# tps79333.net
KiCad netlist of a schematic drawn in Altium Designer
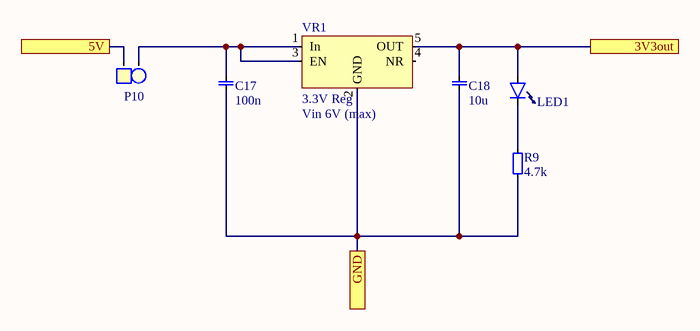
[diagram p0: tps79333.SchDoc]

(export (version "E")
  (design (tool "Eeschema 10.0.6"))
  (components
    (comp (ref "C17")
      (value "100n")
      (footprint "1206, capasitor")
      (fields (field (name "Comment") "1206, capacitor"))
      (libsource (lib "eitp15_lab1_lib") (part "1206, capacitor"))
    )
    (comp (ref "C18")
      (value "10u")
      (footprint "1206, capasitor")
      (fields (field (name "Comment") "1206, capacitor"))
      (libsource (lib "eitp15_lab1_lib") (part "1206, capacitor"))
    )
    (comp (ref "LED1")
      (value "0805, LED")
      (footprint "0805_led")
      (libsource (lib "eitp15_lab1_lib") (part "0805, LED"))
    )
    (comp (ref "P10")
      (value "1x2 Pin Header")
      (footprint "1x2HEADER")
      (description "2.54 mm, TH")
      (libsource (lib "eitp15_lab1_lib") (part "1x2 Pin Header"))
    )
    (comp (ref "R9")
      (value "4.7k")
      (footprint "1206")
      (description "Resistor")
      (fields (field (name "Comment") "1206, resistor"))
      (libsource (lib "eitp15_lab1_lib") (part "1206, resistor"))
    )
    (comp (ref "VR1")
      (value "3.3V Reg")
      (footprint "SOT23-5")
      (description "3.3V Reg, Ultra-Low Noise, 200 mA")
      (fields (field (name "INPUT VOLTAGE") "Vin 6V (max)"))
      (libsource (lib "eitp15_lab1_lib") (part "TPS79333DBR"))
    )
  )
  (nets
    (net (code "1") (name "/3V3out") (class "Default")
      (node (ref "C18") (pin "1") (pinfunction "1_1") (pintype "passive"))
      (node (ref "LED1") (pin "1") (pinfunction "1_1") (pintype "passive"))
      (node (ref "VR1") (pin "5") (pinfunction "OUT_5") (pintype "passive"))
    )
    (net (code "2") (name "/5V") (class "Default")
      (node (ref "P10") (pin "1") (pinfunction "1_1") (pintype "passive"))
    )
    (net (code "3") (name "/GND") (class "Default")
      (node (ref "C17") (pin "0") (pinfunction "0_0") (pintype "passive"))
      (node (ref "C18") (pin "0") (pinfunction "0_0") (pintype "passive"))
      (node (ref "R9") (pin "1") (pinfunction "1_1") (pintype "passive"))
      (node (ref "VR1") (pin "2") (pinfunction "GND_2") (pintype "passive"))
    )
    (net (code "4") (name "Net-(LED1-Cathode)") (class "Default")
      (node (ref "LED1") (pin "0") (pinfunction "Cathode_0") (pintype "passive"))
      (node (ref "R9") (pin "0") (pinfunction "0_0") (pintype "passive"))
    )
    (net (code "5") (name "Net-(VR1-EN)") (class "Default")
      (node (ref "C17") (pin "1") (pinfunction "1_1") (pintype "passive"))
      (node (ref "P10") (pin "2") (pinfunction "2_2") (pintype "passive"))
      (node (ref "VR1") (pin "1") (pinfunction "In_1") (pintype "passive"))
      (node (ref "VR1") (pin "3") (pinfunction "EN_3") (pintype "passive"))
    )
    (net (code "6") (name "unconnected-(VR1-NR-Pad4)") (class "Default")
      (node (ref "VR1") (pin "4") (pinfunction "NR_4") (pintype "passive"))
    )
  )
)
